# 36V_Supply.net
KiCad netlist of a schematic drawn in Altium Designer
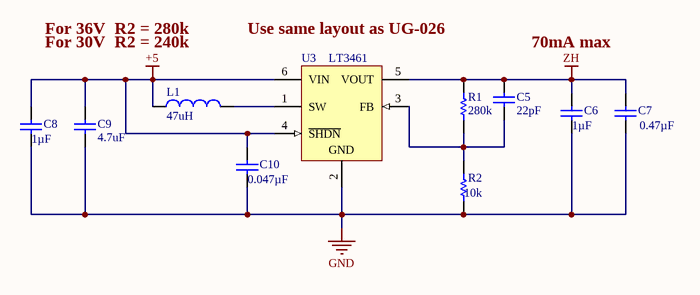
[diagram p0: 36V_Supply.SchDoc]

(export (version "E")
  (design (tool "Eeschema 10.0.6"))
  (components
    (comp (ref "C5")
      (value "22pF")
      (footprint "CAPC1206(3216)170_L")
      (description "CAP CER 22PF 50V C0G/NP0 1206")
      (fields
        (field (name "MANUFACTURER") "KEMET")
        (field (name "MANUFACTURER PART NUMBER") "C1206C220K5GACTU")
      )
      (libsource (lib "Altium Content Vault") (part "CMP-1037-04573-1"))
    )
    (comp (ref "C6")
      (value "CAP CER 1UF 50V X7R 1210")
      (footprint "CAPC1210(3225)100_N")
      (fields
        (field (name "MANUFACTURER") "Taiyo Yuden")
        (field (name "MANUFACTURER PART NUMBER") "UMK325B7105KH-T")
        (field (name "CAPACITANCE") "1µF")
        (field (name "TOLERANCE") "±10%")
      )
      (libsource (lib "Altium Content Vault") (part "CMP-1038-01123-1"))
    )
    (comp (ref "C7")
      (value "CAP CER 0.47UF 50V X7R 1206")
      (footprint "CAPC1206(3216)190_N")
      (fields
        (field (name "MANUFACTURER") "Taiyo Yuden")
        (field (name "MANUFACTURER PART NUMBER") "UMK316B7474KL-T")
        (field (name "CAPACITANCE") "0.47µF")
        (field (name "TOLERANCE") "±10%")
      )
      (libsource (lib "Altium Content Vault") (part "CMP-1037-04570-1"))
    )
    (comp (ref "C8")
      (value "CAP CER 1UF 16V X7R 0805")
      (footprint "CAPC0805(2012)145_N")
      (fields
        (field (name "MANUFACTURER") "Taiyo Yuden")
        (field (name "MANUFACTURER PART NUMBER") "EMK212B7105KG-T")
        (field (name "CAPACITANCE") "1µF")
        (field (name "TOLERANCE") "±10%")
      )
      (libsource (lib "Altium Content Vault") (part "CMP-1036-04795-1"))
    )
    (comp (ref "C9")
      (value "4.7uF")
      (footprint "CAPC0805(2012)145_M")
      (description "CAP CER 4.7UF 16V X7R 0805")
      (fields
        (field (name "MANUFACTURER") "KEMET")
        (field (name "MANUFACTURER PART NUMBER") "C0805C475K4RACTU")
      )
      (libsource (lib "Altium Content Vault") (part "CMP-1036-04750-1"))
    )
    (comp (ref "C10")
      (value "CAP CER 0.047UF 16V X7R 0603")
      (footprint "CAPC0805(2012)145_N")
      (fields
        (field (name "MANUFACTURER") "Murata Electronics North America")
        (field (name "MANUFACTURER PART NUMBER") "GRM188R71C473KA01D")
        (field (name "CAPACITANCE") "0.047µF")
        (field (name "TOLERANCE") "±10%")
      )
      (libsource (lib "Altium Content Vault") (part "CMP-1036-04795-1"))
    )
    (comp (ref "L1")
      (value "47uH")
      (footprint "C1210")
      (description "FIXED IND 47UH 170MA 1.3 OHM SMD")
      (fields
        (field (name "MANUFACTURER") "Murata Electronics North America")
        (field (name "MANUFACTURER PART NUMBER") "LQH32CN470K23L")
      )
      (libsource (lib "Miscellaneous Devices") (part "Inductor"))
    )
    (comp (ref "R1")
      (value "RES SMD 280K OHM 1% 1/8W 0805")
      (footprint "RESC0805(2012)_M")
      (fields
        (field (name "MANUFACTURER") "Vishay Dale")
        (field (name "MANUFACTURER PART NUMBER") "CRCW0805280KFKEA")
        (field (name "RESISTANCE (OHMS)") "280k")
        (field (name "TOLERANCE") "±1%")
      )
      (libsource (lib "Altium Content Vault") (part "CMP-1013-00017-1"))
    )
    (comp (ref "R2")
      (value "RES SMD 10K OHM 1% 1/8W 0805")
      (footprint "RESC0805(2012)_M")
      (fields
        (field (name "MANUFACTURER") "Yageo")
        (field (name "MANUFACTURER PART NUMBER") "RC0805FR-0710KL")
        (field (name "RESISTANCE (OHMS)") "10k")
        (field (name "TOLERANCE") "±1%")
      )
      (libsource (lib "Altium Content Vault") (part "CMP-1013-00017-1"))
    )
    (comp (ref "U3")
      (value "LT3461")
      (footprint "LT-S6-6-TSOT-23_N")
      (description "IC REG BOOST ADJ 0.3A TSOT23-6")
      (libsource (lib "Altium Content Vault") (part "CMP-0491-01698-1"))
    )
  )
  (nets
    (net (code "1") (name "+5") (class "Default")
      (node (ref "C10") (pin "2") (pinfunction "2_2") (pintype "passive"))
      (node (ref "C8") (pin "2") (pinfunction "2_2") (pintype "passive"))
      (node (ref "C9") (pin "2") (pinfunction "2_2") (pintype "passive"))
      (node (ref "L1") (pin "1") (pinfunction "1_1") (pintype "passive"))
      (node (ref "U3") (pin "4") (pinfunction "~{SHDN}_4") (pintype "input"))
      (node (ref "U3") (pin "6") (pinfunction "VIN_6") (pintype "power_in"))
    )
    (net (code "2") (name "GND") (class "Default")
      (node (ref "C10") (pin "1") (pinfunction "1_1") (pintype "passive"))
      (node (ref "C6") (pin "1") (pinfunction "1_1") (pintype "passive"))
      (node (ref "C7") (pin "1") (pinfunction "1_1") (pintype "passive"))
      (node (ref "C8") (pin "1") (pinfunction "1_1") (pintype "passive"))
      (node (ref "C9") (pin "1") (pinfunction "1_1") (pintype "passive"))
      (node (ref "R2") (pin "2") (pinfunction "2_2") (pintype "passive"))
      (node (ref "U3") (pin "2") (pinfunction "GND_2") (pintype "power_in"))
    )
    (net (code "3") (name "Net-(U3-FB)") (class "Default")
      (node (ref "C5") (pin "1") (pinfunction "1_1") (pintype "passive"))
      (node (ref "R1") (pin "2") (pinfunction "2_2") (pintype "passive"))
      (node (ref "R2") (pin "1") (pinfunction "1_1") (pintype "passive"))
      (node (ref "U3") (pin "3") (pinfunction "FB_3") (pintype "input"))
    )
    (net (code "4") (name "Net-(U3-SW)") (class "Default")
      (node (ref "L1") (pin "2") (pinfunction "2_2") (pintype "passive"))
      (node (ref "U3") (pin "1") (pinfunction "SW_1") (pintype "passive"))
    )
    (net (code "5") (name "ZH") (class "Default")
      (node (ref "C5") (pin "2") (pinfunction "2_2") (pintype "passive"))
      (node (ref "C6") (pin "2") (pinfunction "2_2") (pintype "passive"))
      (node (ref "C7") (pin "2") (pinfunction "2_2") (pintype "passive"))
      (node (ref "R1") (pin "1") (pinfunction "1_1") (pintype "passive"))
      (node (ref "U3") (pin "5") (pinfunction "VOUT_5") (pintype "power_in"))
    )
  )
)
